# LoRa.net
KiCad netlist of a schematic drawn in Altium Designer
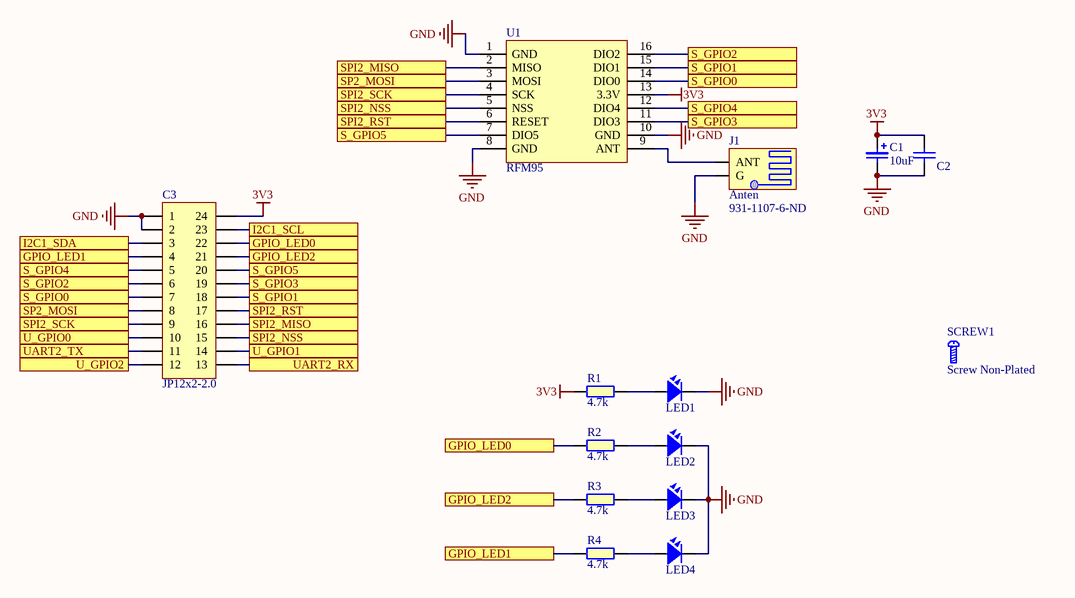
[diagram p0: LoRa.SchDoc]

(export (version "E")
  (design (tool "Eeschema 10.0.6"))
  (components
    (comp (ref "C1")
      (value "10uF")
      (footprint "CASE A")
      (description "CAP TANT 10UF 16V 10% 2917")
      (fields (field (name "PART NUMBER") "T491A106K010AT") (field (name "VOLTAGE") "10VDC"))
      (libsource (lib "Node") (part "Capacitor-Tantalium"))
    )
    (comp (ref "C2") (value "0.01uF") (footprint "C_0603") (libsource (lib "Node") (part "CAP_0603")))
    (comp (ref "C3")
      (value "JP12x2-2.0")
      (footprint "J12-C2T")
      (description "WR-PHD 2.00 mm Dual Pin Header")
      (fields
        (field (name "MANUFACTURER") "Würth Elektronik eiSos GmbH")
        (field (name "PARTNO") "62002421121")
        (field (name "CREATED BY") "Karrer Zheng")
      )
      (libsource (lib "LIBRARY") (part "JP12x2-2.0"))
    )
    (comp (ref "J1")
      (value "Anten")
      (footprint "ANTEN_IPEX")
      (description "CONN UMC RCPT STR 50 OHM SMD")
      (fields
        (field (name "SUPPLIER PART NUMBER 1") "931-1107-6-ND")
        (field (name "MANUFACTURER") "Taoglas")
        (field (name "MANUFACTURER PART NUMBER") "RECE.20279.001E.01")
      )
      (libsource (lib "Node") (part "ANTEN_IPEX"))
    )
    (comp (ref "LED1")
      (value "LED")
      (footprint "LED-3MM-RED")
      (description "LED Single colour Green and Red")
      (libsource (lib "LIBRARY") (part "LED"))
    )
    (comp (ref "LED2")
      (value "LED")
      (footprint "LED-3MM-GREEN")
      (description "LED Single colour Green and Red")
      (libsource (lib "LIBRARY") (part "LED"))
    )
    (comp (ref "LED3")
      (value "LED")
      (footprint "LED-3MM-BLUE")
      (description "LED Single colour Green and Red")
      (libsource (lib "LIBRARY") (part "LED"))
    )
    (comp (ref "LED4")
      (value "LED")
      (footprint "LED-3MM-YELLOW")
      (description "LED Single colour Green and Red")
      (libsource (lib "LIBRARY") (part "LED"))
    )
    (comp (ref "R1") (value "4.7k") (footprint "R_0603") (libsource (lib "Node") (part "RES_0603")))
    (comp (ref "R2") (value "4.7k") (footprint "R_0603") (libsource (lib "Node") (part "RES_0603")))
    (comp (ref "R3") (value "4.7k") (footprint "R_0603") (libsource (lib "Node") (part "RES_0603")))
    (comp (ref "R4") (value "4.7k") (footprint "R_0603") (libsource (lib "Node") (part "RES_0603")))
    (comp (ref "SCREW1")
      (value "Screw Non-Plated")
      (footprint "ThanhNT:SCREW_NON-PLATED_2MM")
      (libsource (lib "ThanhNT") (part "SCREW_NON-PLATED"))
    )
    (comp (ref "U1")
      (value "RFM95")
      (footprint "RFM95")
      (description "RFM95 ULTRA-LONG RANGE TRANSCEIV")
      (fields
        (field (name "MANUFACTURER") "Seeed Studio")
        (field (name "MANUFACTURER PART NUMBER") "109990166")
      )
      (libsource (lib "Node") (part "RFM95"))
    )
  )
  (nets
    (net (code "1") (name "/GPIO_LED0") (class "Default")
      (node (ref "C3") (pin "22") (pinfunction "22_22") (pintype "passive"))
      (node (ref "R2") (pin "1") (pinfunction "1_1") (pintype "passive"))
    )
    (net (code "2") (name "/GPIO_LED1") (class "Default")
      (node (ref "C3") (pin "4") (pinfunction "4_4") (pintype "passive"))
      (node (ref "R4") (pin "1") (pinfunction "1_1") (pintype "passive"))
    )
    (net (code "3") (name "/GPIO_LED2") (class "Default")
      (node (ref "C3") (pin "21") (pinfunction "21_21") (pintype "passive"))
      (node (ref "R3") (pin "1") (pinfunction "1_1") (pintype "passive"))
    )
    (net (code "4") (name "/I2C1_SCL") (class "Default")
      (node (ref "C3") (pin "23") (pinfunction "23_23") (pintype "passive"))
    )
    (net (code "5") (name "/I2C1_SDA") (class "Default")
      (node (ref "C3") (pin "3") (pinfunction "3_3") (pintype "passive"))
    )
    (net (code "6") (name "/SP2_MOSI") (class "Default")
      (node (ref "C3") (pin "8") (pinfunction "8_8") (pintype "passive"))
      (node (ref "U1") (pin "3") (pinfunction "MOSI_3") (pintype "passive"))
    )
    (net (code "7") (name "/SPI2_MISO") (class "Default")
      (node (ref "C3") (pin "16") (pinfunction "16_16") (pintype "passive"))
      (node (ref "U1") (pin "2") (pinfunction "MISO_2") (pintype "passive"))
    )
    (net (code "8") (name "/SPI2_NSS") (class "Default")
      (node (ref "C3") (pin "15") (pinfunction "15_15") (pintype "passive"))
      (node (ref "U1") (pin "5") (pinfunction "NSS_5") (pintype "passive"))
    )
    (net (code "9") (name "/SPI2_RST") (class "Default")
      (node (ref "C3") (pin "17") (pinfunction "17_17") (pintype "passive"))
      (node (ref "U1") (pin "6") (pinfunction "RESET_6") (pintype "passive"))
    )
    (net (code "10") (name "/SPI2_SCK") (class "Default")
      (node (ref "C3") (pin "9") (pinfunction "9_9") (pintype "passive"))
      (node (ref "U1") (pin "4") (pinfunction "SCK_4") (pintype "passive"))
    )
    (net (code "11") (name "/S_GPIO0") (class "Default")
      (node (ref "C3") (pin "7") (pinfunction "7_7") (pintype "passive"))
      (node (ref "U1") (pin "14") (pinfunction "DIO0_14") (pintype "passive"))
    )
    (net (code "12") (name "/S_GPIO1") (class "Default")
      (node (ref "C3") (pin "18") (pinfunction "18_18") (pintype "passive"))
      (node (ref "U1") (pin "15") (pinfunction "DIO1_15") (pintype "passive"))
    )
    (net (code "13") (name "/S_GPIO2") (class "Default")
      (node (ref "C3") (pin "6") (pinfunction "6_6") (pintype "passive"))
      (node (ref "U1") (pin "16") (pinfunction "DIO2_16") (pintype "passive"))
    )
    (net (code "14") (name "/S_GPIO3") (class "Default")
      (node (ref "C3") (pin "19") (pinfunction "19_19") (pintype "passive"))
      (node (ref "U1") (pin "11") (pinfunction "DIO3_11") (pintype "passive"))
    )
    (net (code "15") (name "/S_GPIO4") (class "Default")
      (node (ref "C3") (pin "5") (pinfunction "5_5") (pintype "passive"))
      (node (ref "U1") (pin "12") (pinfunction "DIO4_12") (pintype "passive"))
    )
    (net (code "16") (name "/S_GPIO5") (class "Default")
      (node (ref "C3") (pin "20") (pinfunction "20_20") (pintype "passive"))
      (node (ref "U1") (pin "7") (pinfunction "DIO5_7") (pintype "passive"))
    )
    (net (code "17") (name "/UART2_RX") (class "Default")
      (node (ref "C3") (pin "13") (pinfunction "13_13") (pintype "passive"))
    )
    (net (code "18") (name "/UART2_TX") (class "Default")
      (node (ref "C3") (pin "11") (pinfunction "11_11") (pintype "passive"))
    )
    (net (code "19") (name "/U_GPIO0") (class "Default")
      (node (ref "C3") (pin "10") (pinfunction "10_10") (pintype "passive"))
    )
    (net (code "20") (name "/U_GPIO1") (class "Default")
      (node (ref "C3") (pin "14") (pinfunction "14_14") (pintype "passive"))
    )
    (net (code "21") (name "/U_GPIO2") (class "Default")
      (node (ref "C3") (pin "12") (pinfunction "12_12") (pintype "passive"))
    )
    (net (code "22") (name "3V3") (class "Default")
      (node (ref "C1") (pin "A") (pinfunction "A_A") (pintype "passive"))
      (node (ref "C2") (pin "2") (pinfunction "2_2") (pintype "passive"))
      (node (ref "C3") (pin "24") (pinfunction "24_24") (pintype "passive"))
      (node (ref "R1") (pin "1") (pinfunction "1_1") (pintype "passive"))
      (node (ref "U1") (pin "13") (pinfunction "3.3V_13") (pintype "passive"))
    )
    (net (code "23") (name "GND") (class "Default")
      (node (ref "C1") (pin "K") (pinfunction "K_K") (pintype "passive"))
      (node (ref "C2") (pin "1") (pinfunction "1_1") (pintype "passive"))
      (node (ref "C3") (pin "1") (pinfunction "1_1") (pintype "passive"))
      (node (ref "C3") (pin "2") (pinfunction "2_2") (pintype "passive"))
      (node (ref "J1") (pin "2") (pinfunction "G_2") (pintype "passive"))
      (node (ref "LED1") (pin "2") (pinfunction "2_2") (pintype "passive"))
      (node (ref "LED2") (pin "2") (pinfunction "2_2") (pintype "passive"))
      (node (ref "LED3") (pin "2") (pinfunction "2_2") (pintype "passive"))
      (node (ref "LED4") (pin "2") (pinfunction "2_2") (pintype "passive"))
      (node (ref "U1") (pin "1") (pinfunction "GND_1") (pintype "passive"))
      (node (ref "U1") (pin "10") (pinfunction "GND_10") (pintype "passive"))
      (node (ref "U1") (pin "8") (pinfunction "GND_8") (pintype "passive"))
    )
    (net (code "24") (name "Net-(J1-ANT)") (class "Default")
      (node (ref "J1") (pin "1") (pinfunction "ANT_1") (pintype "passive"))
      (node (ref "U1") (pin "9") (pinfunction "ANT_9") (pintype "passive"))
    )
    (net (code "25") (name "Net-(LED1-Pad1)") (class "Default")
      (node (ref "LED1") (pin "1") (pinfunction "1_1") (pintype "passive"))
      (node (ref "R1") (pin "2") (pinfunction "2_2") (pintype "passive"))
    )
    (net (code "26") (name "Net-(LED2-Pad1)") (class "Default")
      (node (ref "LED2") (pin "1") (pinfunction "1_1") (pintype "passive"))
      (node (ref "R2") (pin "2") (pinfunction "2_2") (pintype "passive"))
    )
    (net (code "27") (name "Net-(LED3-Pad1)") (class "Default")
      (node (ref "LED3") (pin "1") (pinfunction "1_1") (pintype "passive"))
      (node (ref "R3") (pin "2") (pinfunction "2_2") (pintype "passive"))
    )
    (net (code "28") (name "Net-(LED4-Pad1)") (class "Default")
      (node (ref "LED4") (pin "1") (pinfunction "1_1") (pintype "passive"))
      (node (ref "R4") (pin "2") (pinfunction "2_2") (pintype "passive"))
    )
  )
)
